# MCU.net
KiCad netlist of a schematic drawn in Altium Designer
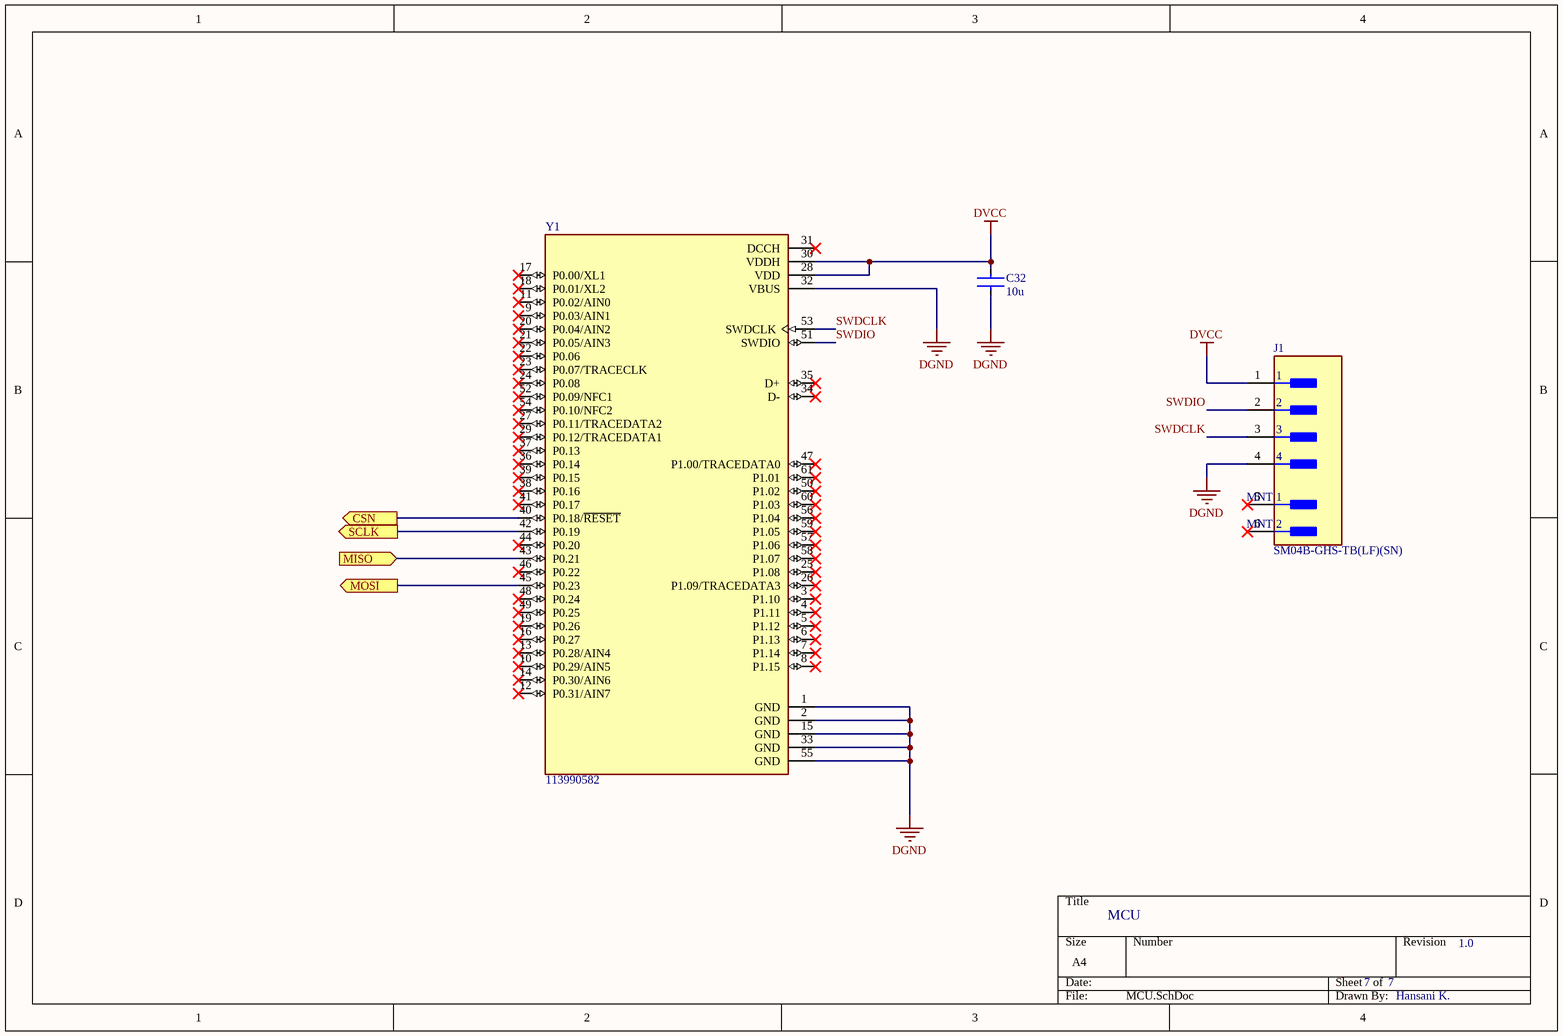
[diagram p0: MCU.SchDoc]

(export (version "E")
  (design (tool "Eeschema 10.0.6"))
  (components
    (comp (ref "C32")
      (value "10u")
      (footprint "PCBComponent_1")
      (description "Surface Mount Tantalum Capacitor, 10 uF, 10 V, ± 10%, -55 °C, 125 °C, 0805 [2012-15 Metric]")
      (fields
        (field (name "MANUFACTURER") "Vishay")
        (field (name "MANUFACTURER PART NUMBER") "TM8R106K010UBA")
      )
      (libsource (lib "Schlib1") (part "TM8R106K010UBA"))
    )
    (comp (ref "J1")
      (value "SM04B-GHS-TB(LF)(SN)")
      (footprint "FP-SM04B-GHS-TB_LF_SN-MFG")
      (description "CONN HEADER SMD R/A 4POS 1.25MM")
      (libsource (lib "Altium Content Vault") (part "f4320a1371cd6270e33bce1916c33c0"))
    )
    (comp (ref "Y1")
      (value "113990582")
      (footprint "XCVR_MDBT50Q-1MV2")
      (description "Bluetooth v4.2 (BLE)/v5.0 SMART SOC 2Mbps 61-Pin SMD Module")
      (fields (field (name "MANUFACTURER") "Seeed Studio"))
      (libsource (lib "Schlib1") (part "113990582"))
    )
  )
  (nets
    (net (code "1") (name "/CSN") (class "Default")
      (node (ref "Y1") (pin "40") (pinfunction "P0.18/~{RESET}_40") (pintype "bidirectional"))
    )
    (net (code "2") (name "/MISO") (class "Default")
      (node (ref "Y1") (pin "43") (pinfunction "P0.21_43") (pintype "bidirectional"))
    )
    (net (code "3") (name "/MOSI") (class "Default")
      (node (ref "Y1") (pin "45") (pinfunction "P0.23_45") (pintype "bidirectional"))
    )
    (net (code "4") (name "/SCLK") (class "Default")
      (node (ref "Y1") (pin "42") (pinfunction "P0.19_42") (pintype "bidirectional"))
    )
    (net (code "5") (name "/SWDCLK") (class "Default")
      (node (ref "J1") (pin "3") (pinfunction "3_3") (pintype "passive"))
      (node (ref "Y1") (pin "53") (pinfunction "SWDCLK_53") (pintype "input"))
    )
    (net (code "6") (name "/SWDIO") (class "Default")
      (node (ref "J1") (pin "2") (pinfunction "2_2") (pintype "passive"))
      (node (ref "Y1") (pin "51") (pinfunction "SWDIO_51") (pintype "bidirectional"))
    )
    (net (code "7") (name "DGND") (class "Default")
      (node (ref "C32") (pin "1") (pinfunction "1_1") (pintype "passive"))
      (node (ref "J1") (pin "4") (pinfunction "4_4") (pintype "passive"))
      (node (ref "Y1") (pin "1") (pinfunction "GND_1") (pintype "power_in"))
      (node (ref "Y1") (pin "15") (pinfunction "GND_15") (pintype "power_in"))
      (node (ref "Y1") (pin "2") (pinfunction "GND_2") (pintype "power_in"))
      (node (ref "Y1") (pin "32") (pinfunction "VBUS_32") (pintype "power_in"))
      (node (ref "Y1") (pin "33") (pinfunction "GND_33") (pintype "power_in"))
      (node (ref "Y1") (pin "55") (pinfunction "GND_55") (pintype "power_in"))
    )
    (net (code "8") (name "DVCC") (class "Default")
      (node (ref "C32") (pin "2") (pinfunction "2_2") (pintype "passive"))
      (node (ref "J1") (pin "1") (pinfunction "1_1") (pintype "passive"))
      (node (ref "Y1") (pin "28") (pinfunction "VDD_28") (pintype "power_in"))
      (node (ref "Y1") (pin "30") (pinfunction "VDDH_30") (pintype "power_in"))
    )
    (net (code "9") (name "unconnected-(J1-MNT_1-Pad5)") (class "Default")
      (node (ref "J1") (pin "5") (pinfunction "MNT_1_5") (pintype "passive+no_connect"))
    )
    (net (code "10") (name "unconnected-(J1-MNT_2-Pad6)") (class "Default")
      (node (ref "J1") (pin "6") (pinfunction "MNT_2_6") (pintype "passive+no_connect"))
    )
    (net (code "11") (name "unconnected-(Y1-D+-Pad35)") (class "Default")
      (node (ref "Y1") (pin "35") (pinfunction "D+_35") (pintype "bidirectional+no_connect"))
    )
    (net (code "12") (name "unconnected-(Y1-D--Pad34)") (class "Default")
      (node (ref "Y1") (pin "34") (pinfunction "D-_34") (pintype "bidirectional+no_connect"))
    )
    (net (code "13") (name "unconnected-(Y1-DCCH-Pad31)") (class "Default")
      (node (ref "Y1") (pin "31") (pinfunction "DCCH_31") (pintype "power_in+no_connect"))
    )
    (net (code "14") (name "unconnected-(Y1-P0.00{slash}XL1-Pad17)") (class "Default")
      (node (ref "Y1") (pin "17") (pinfunction "P0.00/XL1_17") (pintype "bidirectional+no_connect"))
    )
    (net (code "15") (name "unconnected-(Y1-P0.01{slash}XL2-Pad18)") (class "Default")
      (node (ref "Y1") (pin "18") (pinfunction "P0.01/XL2_18") (pintype "bidirectional+no_connect"))
    )
    (net (code "16") (name "unconnected-(Y1-P0.02{slash}AIN0-Pad11)") (class "Default")
      (node (ref "Y1") (pin "11") (pinfunction "P0.02/AIN0_11") (pintype "bidirectional+no_connect"))
    )
    (net (code "17") (name "unconnected-(Y1-P0.03{slash}AIN1-Pad9)") (class "Default")
      (node (ref "Y1") (pin "9") (pinfunction "P0.03/AIN1_9") (pintype "bidirectional+no_connect"))
    )
    (net (code "18") (name "unconnected-(Y1-P0.04{slash}AIN2-Pad20)") (class "Default")
      (node (ref "Y1") (pin "20") (pinfunction "P0.04/AIN2_20") (pintype "bidirectional+no_connect"))
    )
    (net (code "19") (name "unconnected-(Y1-P0.05{slash}AIN3-Pad21)") (class "Default")
      (node (ref "Y1") (pin "21") (pinfunction "P0.05/AIN3_21") (pintype "bidirectional+no_connect"))
    )
    (net (code "20") (name "unconnected-(Y1-P0.06-Pad22)") (class "Default")
      (node (ref "Y1") (pin "22") (pinfunction "P0.06_22") (pintype "bidirectional+no_connect"))
    )
    (net (code "21") (name "unconnected-(Y1-P0.07{slash}TRACECLK-Pad23)") (class "Default")
      (node (ref "Y1") (pin "23") (pinfunction "P0.07/TRACECLK_23") (pintype "bidirectional+no_connect"))
    )
    (net (code "22") (name "unconnected-(Y1-P0.08-Pad24)") (class "Default")
      (node (ref "Y1") (pin "24") (pinfunction "P0.08_24") (pintype "bidirectional+no_connect"))
    )
    (net (code "23") (name "unconnected-(Y1-P0.09{slash}NFC1-Pad52)") (class "Default")
      (node (ref "Y1") (pin "52") (pinfunction "P0.09/NFC1_52") (pintype "bidirectional+no_connect"))
    )
    (net (code "24") (name "unconnected-(Y1-P0.10{slash}NFC2-Pad54)") (class "Default")
      (node (ref "Y1") (pin "54") (pinfunction "P0.10/NFC2_54") (pintype "bidirectional+no_connect"))
    )
    (net (code "25") (name "unconnected-(Y1-P0.11{slash}TRACEDATA2-Pad27)") (class "Default")
      (node (ref "Y1") (pin "27") (pinfunction "P0.11/TRACEDATA2_27") (pintype "bidirectional+no_connect"))
    )
    (net (code "26") (name "unconnected-(Y1-P0.12{slash}TRACEDATA1-Pad29)") (class "Default")
      (node (ref "Y1") (pin "29") (pinfunction "P0.12/TRACEDATA1_29") (pintype "bidirectional+no_connect"))
    )
    (net (code "27") (name "unconnected-(Y1-P0.13-Pad37)") (class "Default")
      (node (ref "Y1") (pin "37") (pinfunction "P0.13_37") (pintype "bidirectional+no_connect"))
    )
    (net (code "28") (name "unconnected-(Y1-P0.14-Pad36)") (class "Default")
      (node (ref "Y1") (pin "36") (pinfunction "P0.14_36") (pintype "bidirectional+no_connect"))
    )
    (net (code "29") (name "unconnected-(Y1-P0.15-Pad39)") (class "Default")
      (node (ref "Y1") (pin "39") (pinfunction "P0.15_39") (pintype "bidirectional+no_connect"))
    )
    (net (code "30") (name "unconnected-(Y1-P0.16-Pad38)") (class "Default")
      (node (ref "Y1") (pin "38") (pinfunction "P0.16_38") (pintype "bidirectional+no_connect"))
    )
    (net (code "31") (name "unconnected-(Y1-P0.17-Pad41)") (class "Default")
      (node (ref "Y1") (pin "41") (pinfunction "P0.17_41") (pintype "bidirectional+no_connect"))
    )
    (net (code "32") (name "unconnected-(Y1-P0.20-Pad44)") (class "Default")
      (node (ref "Y1") (pin "44") (pinfunction "P0.20_44") (pintype "bidirectional+no_connect"))
    )
    (net (code "33") (name "unconnected-(Y1-P0.22-Pad46)") (class "Default")
      (node (ref "Y1") (pin "46") (pinfunction "P0.22_46") (pintype "bidirectional+no_connect"))
    )
    (net (code "34") (name "unconnected-(Y1-P0.24-Pad48)") (class "Default")
      (node (ref "Y1") (pin "48") (pinfunction "P0.24_48") (pintype "bidirectional+no_connect"))
    )
    (net (code "35") (name "unconnected-(Y1-P0.25-Pad49)") (class "Default")
      (node (ref "Y1") (pin "49") (pinfunction "P0.25_49") (pintype "bidirectional+no_connect"))
    )
    (net (code "36") (name "unconnected-(Y1-P0.26-Pad19)") (class "Default")
      (node (ref "Y1") (pin "19") (pinfunction "P0.26_19") (pintype "bidirectional+no_connect"))
    )
    (net (code "37") (name "unconnected-(Y1-P0.27-Pad16)") (class "Default")
      (node (ref "Y1") (pin "16") (pinfunction "P0.27_16") (pintype "bidirectional+no_connect"))
    )
    (net (code "38") (name "unconnected-(Y1-P0.28{slash}AIN4-Pad13)") (class "Default")
      (node (ref "Y1") (pin "13") (pinfunction "P0.28/AIN4_13") (pintype "bidirectional+no_connect"))
    )
    (net (code "39") (name "unconnected-(Y1-P0.29{slash}AIN5-Pad10)") (class "Default")
      (node (ref "Y1") (pin "10") (pinfunction "P0.29/AIN5_10") (pintype "bidirectional+no_connect"))
    )
    (net (code "40") (name "unconnected-(Y1-P0.30{slash}AIN6-Pad14)") (class "Default")
      (node (ref "Y1") (pin "14") (pinfunction "P0.30/AIN6_14") (pintype "bidirectional+no_connect"))
    )
    (net (code "41") (name "unconnected-(Y1-P0.31{slash}AIN7-Pad12)") (class "Default")
      (node (ref "Y1") (pin "12") (pinfunction "P0.31/AIN7_12") (pintype "bidirectional+no_connect"))
    )
    (net (code "42") (name "unconnected-(Y1-P1.00{slash}TRACEDATA0-Pad47)") (class "Default")
      (node (ref "Y1") (pin "47") (pinfunction "P1.00/TRACEDATA0_47") (pintype "bidirectional+no_connect"))
    )
    (net (code "43") (name "unconnected-(Y1-P1.01-Pad61)") (class "Default")
      (node (ref "Y1") (pin "61") (pinfunction "P1.01_61") (pintype "bidirectional+no_connect"))
    )
    (net (code "44") (name "unconnected-(Y1-P1.02-Pad50)") (class "Default")
      (node (ref "Y1") (pin "50") (pinfunction "P1.02_50") (pintype "bidirectional+no_connect"))
    )
    (net (code "45") (name "unconnected-(Y1-P1.03-Pad60)") (class "Default")
      (node (ref "Y1") (pin "60") (pinfunction "P1.03_60") (pintype "bidirectional+no_connect"))
    )
    (net (code "46") (name "unconnected-(Y1-P1.04-Pad56)") (class "Default")
      (node (ref "Y1") (pin "56") (pinfunction "P1.04_56") (pintype "bidirectional+no_connect"))
    )
    (net (code "47") (name "unconnected-(Y1-P1.05-Pad59)") (class "Default")
      (node (ref "Y1") (pin "59") (pinfunction "P1.05_59") (pintype "bidirectional+no_connect"))
    )
    (net (code "48") (name "unconnected-(Y1-P1.06-Pad57)") (class "Default")
      (node (ref "Y1") (pin "57") (pinfunction "P1.06_57") (pintype "bidirectional+no_connect"))
    )
    (net (code "49") (name "unconnected-(Y1-P1.07-Pad58)") (class "Default")
      (node (ref "Y1") (pin "58") (pinfunction "P1.07_58") (pintype "bidirectional+no_connect"))
    )
    (net (code "50") (name "unconnected-(Y1-P1.08-Pad25)") (class "Default")
      (node (ref "Y1") (pin "25") (pinfunction "P1.08_25") (pintype "bidirectional+no_connect"))
    )
    (net (code "51") (name "unconnected-(Y1-P1.09{slash}TRACEDATA3-Pad26)") (class "Default")
      (node (ref "Y1") (pin "26") (pinfunction "P1.09/TRACEDATA3_26") (pintype "bidirectional+no_connect"))
    )
    (net (code "52") (name "unconnected-(Y1-P1.10-Pad3)") (class "Default")
      (node (ref "Y1") (pin "3") (pinfunction "P1.10_3") (pintype "bidirectional+no_connect"))
    )
    (net (code "53") (name "unconnected-(Y1-P1.11-Pad4)") (class "Default")
      (node (ref "Y1") (pin "4") (pinfunction "P1.11_4") (pintype "bidirectional+no_connect"))
    )
    (net (code "54") (name "unconnected-(Y1-P1.12-Pad5)") (class "Default")
      (node (ref "Y1") (pin "5") (pinfunction "P1.12_5") (pintype "bidirectional+no_connect"))
    )
    (net (code "55") (name "unconnected-(Y1-P1.13-Pad6)") (class "Default")
      (node (ref "Y1") (pin "6") (pinfunction "P1.13_6") (pintype "bidirectional+no_connect"))
    )
    (net (code "56") (name "unconnected-(Y1-P1.14-Pad7)") (class "Default")
      (node (ref "Y1") (pin "7") (pinfunction "P1.14_7") (pintype "bidirectional+no_connect"))
    )
    (net (code "57") (name "unconnected-(Y1-P1.15-Pad8)") (class "Default")
      (node (ref "Y1") (pin "8") (pinfunction "P1.15_8") (pintype "bidirectional+no_connect"))
    )
  )
)
